# ELN2_LaboAntenna.net
KiCad netlist of a schematic drawn in Altium Designer
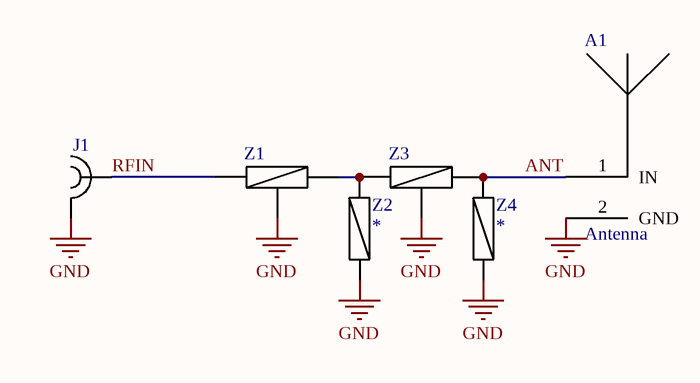
[diagram p0: ELN2_LaboAntenna.SchDoc]

(export (version "E")
  (design (tool "Eeschema 10.0.6"))
  (components
    (comp (ref "A1")
      (value "Antenna")
      (footprint "Antenna")
      (libsource (lib "ELN2_LaboAntenna") (part "Antenna"))
    )
    (comp (ref "J1")
      (value "CONSMA001-G")
      (footprint "SMA EDGE Molex 732511150")
      (description "SMA EDGE Molex 732511150")
      (libsource (lib "Connector") (part "SMA EDGE Molex 732511150"))
    )
    (comp (ref "Z1")
      (value "~")
      (footprint "Matching pad 1005 with Ground")
      (description "Antenna matching pad with ground")
      (libsource (lib "WirelessDevice") (part "Matching pad with ground"))
    )
    (comp (ref "Z2")
      (value "*")
      (footprint "Matching pad 1005")
      (description "Matching pad")
      (libsource (lib "WirelessDevice") (part "Matching pad"))
    )
    (comp (ref "Z3")
      (value "~")
      (footprint "Matching pad 1005 with Ground")
      (description "Antenna matching pad with ground")
      (libsource (lib "WirelessDevice") (part "Matching pad with ground"))
    )
    (comp (ref "Z4")
      (value "*")
      (footprint "Matching pad 1005")
      (description "Matching pad")
      (libsource (lib "WirelessDevice") (part "Matching pad"))
    )
  )
  (nets
    (net (code "1") (name "/ANT") (class "Default")
      (node (ref "A1") (pin "1") (pinfunction "IN_1") (pintype "passive"))
      (node (ref "Z3") (pin "2") (pinfunction "2_2") (pintype "passive"))
      (node (ref "Z4") (pin "2") (pinfunction "2_2") (pintype "passive"))
    )
    (net (code "2") (name "/RFIN") (class "Default")
      (node (ref "J1") (pin "1") (pinfunction "1_1") (pintype "passive"))
      (node (ref "Z1") (pin "1") (pinfunction "1_1") (pintype "passive"))
    )
    (net (code "3") (name "GND") (class "Default")
      (node (ref "A1") (pin "2") (pinfunction "GND_2") (pintype "passive"))
      (node (ref "J1") (pin "2") (pinfunction "2_2") (pintype "passive"))
      (node (ref "Z1") (pin "3") (pinfunction "GND_3") (pintype "passive"))
      (node (ref "Z2") (pin "1") (pinfunction "1_1") (pintype "passive"))
      (node (ref "Z3") (pin "3") (pinfunction "GND_3") (pintype "passive"))
      (node (ref "Z4") (pin "1") (pinfunction "1_1") (pintype "passive"))
    )
    (net (code "4") (name "Net-(Z1-Pad2)") (class "Default")
      (node (ref "Z1") (pin "2") (pinfunction "2_2") (pintype "passive"))
      (node (ref "Z2") (pin "2") (pinfunction "2_2") (pintype "passive"))
      (node (ref "Z3") (pin "1") (pinfunction "1_1") (pintype "passive"))
    )
  )
)
